# ACMon.net
KiCad netlist of a schematic drawn in EAGLE
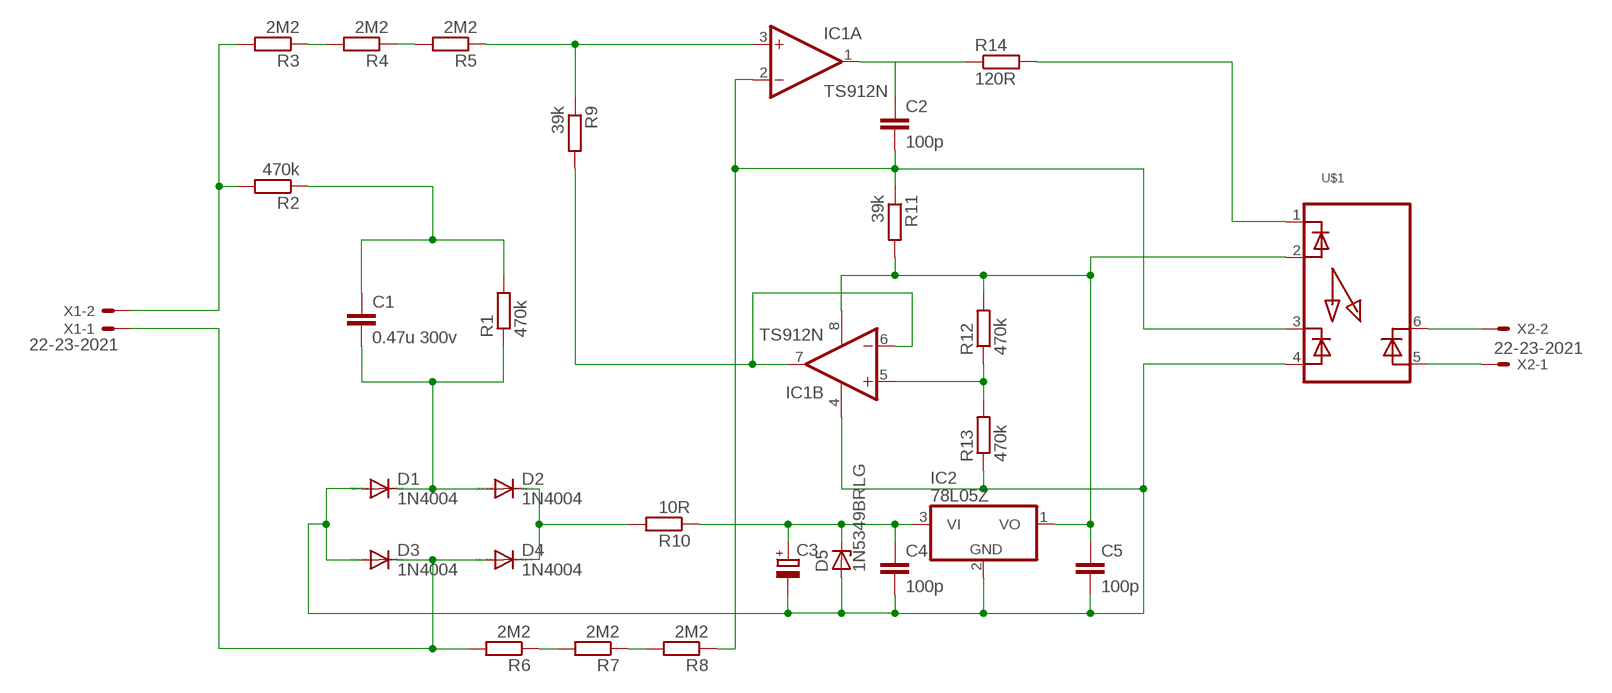
[diagram p0: schematic, sheet 1]

(export (version "E")
  (design (tool "Eeschema 10.0.6"))
  (components
    (comp (ref "C1")
      (value "0.47u 300v")
      (footprint "eagle-import:C275-113X316")
      (libsource (lib "eagle-import") (part "C-EU275-113X316"))
    )
    (comp (ref "C2")
      (value "100p")
      (footprint "eagle-import:C050-025X075")
      (libsource (lib "eagle-import") (part "C-EU050-025X075"))
    )
    (comp (ref "C3")
      (value "CPOL-EUE3.5-8")
      (footprint "eagle-import:E3,5-8")
      (libsource (lib "eagle-import") (part "CPOL-EUE3.5-8"))
    )
    (comp (ref "C4")
      (value "100p")
      (footprint "eagle-import:C050-025X075")
      (libsource (lib "eagle-import") (part "C-EU050-025X075"))
    )
    (comp (ref "C5")
      (value "100p")
      (footprint "eagle-import:C050-025X075")
      (libsource (lib "eagle-import") (part "C-EU050-025X075"))
    )
    (comp (ref "D1")
      (value "1N4004")
      (footprint "eagle-import:DO41-10")
      (libsource (lib "eagle-import") (part "1N4004"))
    )
    (comp (ref "D2")
      (value "1N4004")
      (footprint "eagle-import:DO41-10")
      (libsource (lib "eagle-import") (part "1N4004"))
    )
    (comp (ref "D3")
      (value "1N4004")
      (footprint "eagle-import:DO41-10")
      (libsource (lib "eagle-import") (part "1N4004"))
    )
    (comp (ref "D4")
      (value "1N4004")
      (footprint "eagle-import:DO41-10")
      (libsource (lib "eagle-import") (part "1N4004"))
    )
    (comp (ref "D5")
      (value "1N5349BRLG")
      (footprint "eagle-import:DO41Z10")
      (libsource (lib "eagle-import") (part "1N5349BRLG"))
    )
    (comp (ref "IC1")
      (value "TS912N")
      (footprint "eagle-import:DIL08")
      (libsource (lib "eagle-import") (part "TS912N"))
    )
    (comp (ref "IC2")
      (value "78L05Z")
      (footprint "eagle-import:TO92")
      (libsource (lib "eagle-import") (part "78ZL05"))
    )
    (comp (ref "R1")
      (value "470k")
      (footprint "eagle-import:0309_12")
      (libsource (lib "eagle-import") (part "R-EU_0309/12"))
    )
    (comp (ref "R2")
      (value "470k")
      (footprint "eagle-import:0309_12")
      (libsource (lib "eagle-import") (part "R-EU_0309/12"))
    )
    (comp (ref "R3")
      (value "2M2")
      (footprint "eagle-import:0309_12")
      (libsource (lib "eagle-import") (part "R-EU_0309/12"))
    )
    (comp (ref "R4")
      (value "2M2")
      (footprint "eagle-import:0309_12")
      (libsource (lib "eagle-import") (part "R-EU_0309/12"))
    )
    (comp (ref "R5")
      (value "2M2")
      (footprint "eagle-import:0309_12")
      (libsource (lib "eagle-import") (part "R-EU_0309/12"))
    )
    (comp (ref "R6")
      (value "2M2")
      (footprint "eagle-import:0309_12")
      (libsource (lib "eagle-import") (part "R-EU_0309/12"))
    )
    (comp (ref "R7")
      (value "2M2")
      (footprint "eagle-import:0309_12")
      (libsource (lib "eagle-import") (part "R-EU_0309/12"))
    )
    (comp (ref "R8")
      (value "2M2")
      (footprint "eagle-import:0309_12")
      (libsource (lib "eagle-import") (part "R-EU_0309/12"))
    )
    (comp (ref "R9")
      (value "39k")
      (footprint "eagle-import:0309_12")
      (libsource (lib "eagle-import") (part "R-EU_0309/12"))
    )
    (comp (ref "R10")
      (value "10R")
      (footprint "eagle-import:0309_12")
      (libsource (lib "eagle-import") (part "R-EU_0309/12"))
    )
    (comp (ref "R11")
      (value "39k")
      (footprint "eagle-import:0309_12")
      (libsource (lib "eagle-import") (part "R-EU_0309/12"))
    )
    (comp (ref "R12")
      (value "470k")
      (footprint "eagle-import:0309_12")
      (libsource (lib "eagle-import") (part "R-EU_0309/12"))
    )
    (comp (ref "R13")
      (value "470k")
      (footprint "eagle-import:0309_12")
      (libsource (lib "eagle-import") (part "R-EU_0309/12"))
    )
    (comp (ref "R14")
      (value "120R")
      (footprint "eagle-import:0309_12")
      (libsource (lib "eagle-import") (part "R-EU_0309/12"))
    )
    (comp (ref "U$1")
      (value "IL300")
      (footprint "eagle-import:DIL08")
      (libsource (lib "eagle-import") (part "IL300"))
    )
    (comp (ref "X1")
      (value "22-23-2021")
      (footprint "eagle-import:22-23-2021")
      (fields (field (name "MF") "MOLEX"))
      (libsource (lib "eagle-import") (part "22-23-2021"))
    )
    (comp (ref "X2")
      (value "22-23-2021")
      (footprint "eagle-import:22-23-2021")
      (fields (field (name "MF") "MOLEX"))
      (libsource (lib "eagle-import") (part "22-23-2021"))
    )
  )
  (nets
    (net (code "1") (name "Net-(C1-Pad1)") (class "Default")
      (node (ref "C1") (pin "1") (pinfunction "1_1") (pintype "passive"))
      (node (ref "R1") (pin "2") (pinfunction "2_2") (pintype "passive"))
      (node (ref "R2") (pin "1") (pinfunction "1_1") (pintype "passive"))
    )
    (net (code "2") (name "Net-(C1-Pad2)") (class "Default")
      (node (ref "C1") (pin "2") (pinfunction "2_2") (pintype "passive"))
      (node (ref "D1") (pin "C") (pinfunction "C_C") (pintype "passive"))
      (node (ref "D2") (pin "A") (pinfunction "A_A") (pintype "passive"))
      (node (ref "R1") (pin "1") (pinfunction "1_1") (pintype "passive"))
    )
    (net (code "3") (name "Net-(D2-PadC)") (class "Default")
      (node (ref "D2") (pin "C") (pinfunction "C_C") (pintype "passive"))
      (node (ref "D4") (pin "C") (pinfunction "C_C") (pintype "passive"))
      (node (ref "R10") (pin "2") (pinfunction "2_2") (pintype "passive"))
    )
    (net (code "4") (name "Net-(IC1A-+IN)") (class "Default")
      (node (ref "IC1") (pin "3") (pinfunction "+IN_3") (pintype "input"))
      (node (ref "R5") (pin "1") (pinfunction "1_1") (pintype "passive"))
      (node (ref "R9") (pin "1") (pinfunction "1_1") (pintype "passive"))
    )
    (net (code "5") (name "Net-(IC1A--IN)") (class "Default")
      (node (ref "C2") (pin "2") (pinfunction "2_2") (pintype "passive"))
      (node (ref "IC1") (pin "2") (pinfunction "-IN_2") (pintype "input"))
      (node (ref "R11") (pin "1") (pinfunction "1_1") (pintype "passive"))
      (node (ref "R8") (pin "1") (pinfunction "1_1") (pintype "passive"))
      (node (ref "U$1") (pin "3") (pinfunction "P$3_3") (pintype "passive"))
    )
    (net (code "6") (name "Net-(IC1A-OUT)") (class "Default")
      (node (ref "C2") (pin "1") (pinfunction "1_1") (pintype "passive"))
      (node (ref "IC1") (pin "1") (pinfunction "OUT_1") (pintype "output"))
      (node (ref "R14") (pin "1") (pinfunction "1_1") (pintype "passive"))
    )
    (net (code "7") (name "Net-(IC1B-+IN)") (class "Default")
      (node (ref "IC1") (pin "5") (pinfunction "+IN_5") (pintype "input"))
      (node (ref "R12") (pin "1") (pinfunction "1_1") (pintype "passive"))
      (node (ref "R13") (pin "2") (pinfunction "2_2") (pintype "passive"))
    )
    (net (code "8") (name "Net-(IC1B--IN)") (class "Default")
      (node (ref "IC1") (pin "6") (pinfunction "-IN_6") (pintype "input"))
      (node (ref "IC1") (pin "7") (pinfunction "OUT_7") (pintype "output"))
      (node (ref "R9") (pin "2") (pinfunction "2_2") (pintype "passive"))
    )
    (net (code "9") (name "Net-(IC1C-V+)") (class "Default")
      (node (ref "C5") (pin "1") (pinfunction "1_1") (pintype "passive"))
      (node (ref "IC1") (pin "8") (pinfunction "V+_8") (pintype "power_in"))
      (node (ref "IC2") (pin "1") (pinfunction "VO_1") (pintype "passive"))
      (node (ref "R11") (pin "2") (pinfunction "2_2") (pintype "passive"))
      (node (ref "R12") (pin "2") (pinfunction "2_2") (pintype "passive"))
      (node (ref "U$1") (pin "2") (pinfunction "P$2_2") (pintype "passive"))
    )
    (net (code "10") (name "Net-(IC1C-V-)") (class "Default")
      (node (ref "C3") (pin "-") (pinfunction "-_-") (pintype "passive"))
      (node (ref "C4") (pin "2") (pinfunction "2_2") (pintype "passive"))
      (node (ref "C5") (pin "2") (pinfunction "2_2") (pintype "passive"))
      (node (ref "D1") (pin "A") (pinfunction "A_A") (pintype "passive"))
      (node (ref "D3") (pin "A") (pinfunction "A_A") (pintype "passive"))
      (node (ref "D5") (pin "A") (pinfunction "A_A") (pintype "passive"))
      (node (ref "IC1") (pin "4") (pinfunction "V-_4") (pintype "power_in"))
      (node (ref "IC2") (pin "2") (pinfunction "GND_2") (pintype "passive"))
      (node (ref "R13") (pin "1") (pinfunction "1_1") (pintype "passive"))
      (node (ref "U$1") (pin "4") (pinfunction "P$4_4") (pintype "passive"))
    )
    (net (code "11") (name "Net-(IC2-VI)") (class "Default")
      (node (ref "C3") (pin "+") (pinfunction "+_+") (pintype "passive"))
      (node (ref "C4") (pin "1") (pinfunction "1_1") (pintype "passive"))
      (node (ref "D5") (pin "C") (pinfunction "C_C") (pintype "passive"))
      (node (ref "IC2") (pin "3") (pinfunction "VI_3") (pintype "input"))
      (node (ref "R10") (pin "1") (pinfunction "1_1") (pintype "passive"))
    )
    (net (code "12") (name "Net-(R3-Pad1)") (class "Default")
      (node (ref "R3") (pin "1") (pinfunction "1_1") (pintype "passive"))
      (node (ref "R4") (pin "2") (pinfunction "2_2") (pintype "passive"))
    )
    (net (code "13") (name "Net-(R4-Pad1)") (class "Default")
      (node (ref "R4") (pin "1") (pinfunction "1_1") (pintype "passive"))
      (node (ref "R5") (pin "2") (pinfunction "2_2") (pintype "passive"))
    )
    (net (code "14") (name "Net-(R6-Pad1)") (class "Default")
      (node (ref "R6") (pin "1") (pinfunction "1_1") (pintype "passive"))
      (node (ref "R7") (pin "2") (pinfunction "2_2") (pintype "passive"))
    )
    (net (code "15") (name "Net-(R7-Pad1)") (class "Default")
      (node (ref "R7") (pin "1") (pinfunction "1_1") (pintype "passive"))
      (node (ref "R8") (pin "2") (pinfunction "2_2") (pintype "passive"))
    )
    (net (code "16") (name "Net-(U$1-P$1)") (class "Default")
      (node (ref "R14") (pin "2") (pinfunction "2_2") (pintype "passive"))
      (node (ref "U$1") (pin "1") (pinfunction "P$1_1") (pintype "passive"))
    )
    (net (code "17") (name "Net-(U$1-P$5)") (class "Default")
      (node (ref "U$1") (pin "6") (pinfunction "P$5_6") (pintype "passive"))
      (node (ref "X2") (pin "2") (pinfunction "S_2") (pintype "passive"))
    )
    (net (code "18") (name "Net-(U$1-P$6)") (class "Default")
      (node (ref "U$1") (pin "5") (pinfunction "P$6_5") (pintype "passive"))
      (node (ref "X2") (pin "1") (pinfunction "S_1") (pintype "passive"))
    )
    (net (code "19") (name "Net-(X1A-S)") (class "Default")
      (node (ref "D3") (pin "C") (pinfunction "C_C") (pintype "passive"))
      (node (ref "D4") (pin "A") (pinfunction "A_A") (pintype "passive"))
      (node (ref "R6") (pin "2") (pinfunction "2_2") (pintype "passive"))
      (node (ref "X1") (pin "1") (pinfunction "S_1") (pintype "passive"))
    )
    (net (code "20") (name "Net-(X1B-S)") (class "Default")
      (node (ref "R2") (pin "2") (pinfunction "2_2") (pintype "passive"))
      (node (ref "R3") (pin "2") (pinfunction "2_2") (pintype "passive"))
      (node (ref "X1") (pin "2") (pinfunction "S_2") (pintype "passive"))
    )
  )
)
